# MCU.net
KiCad netlist of a schematic drawn in Altium Designer
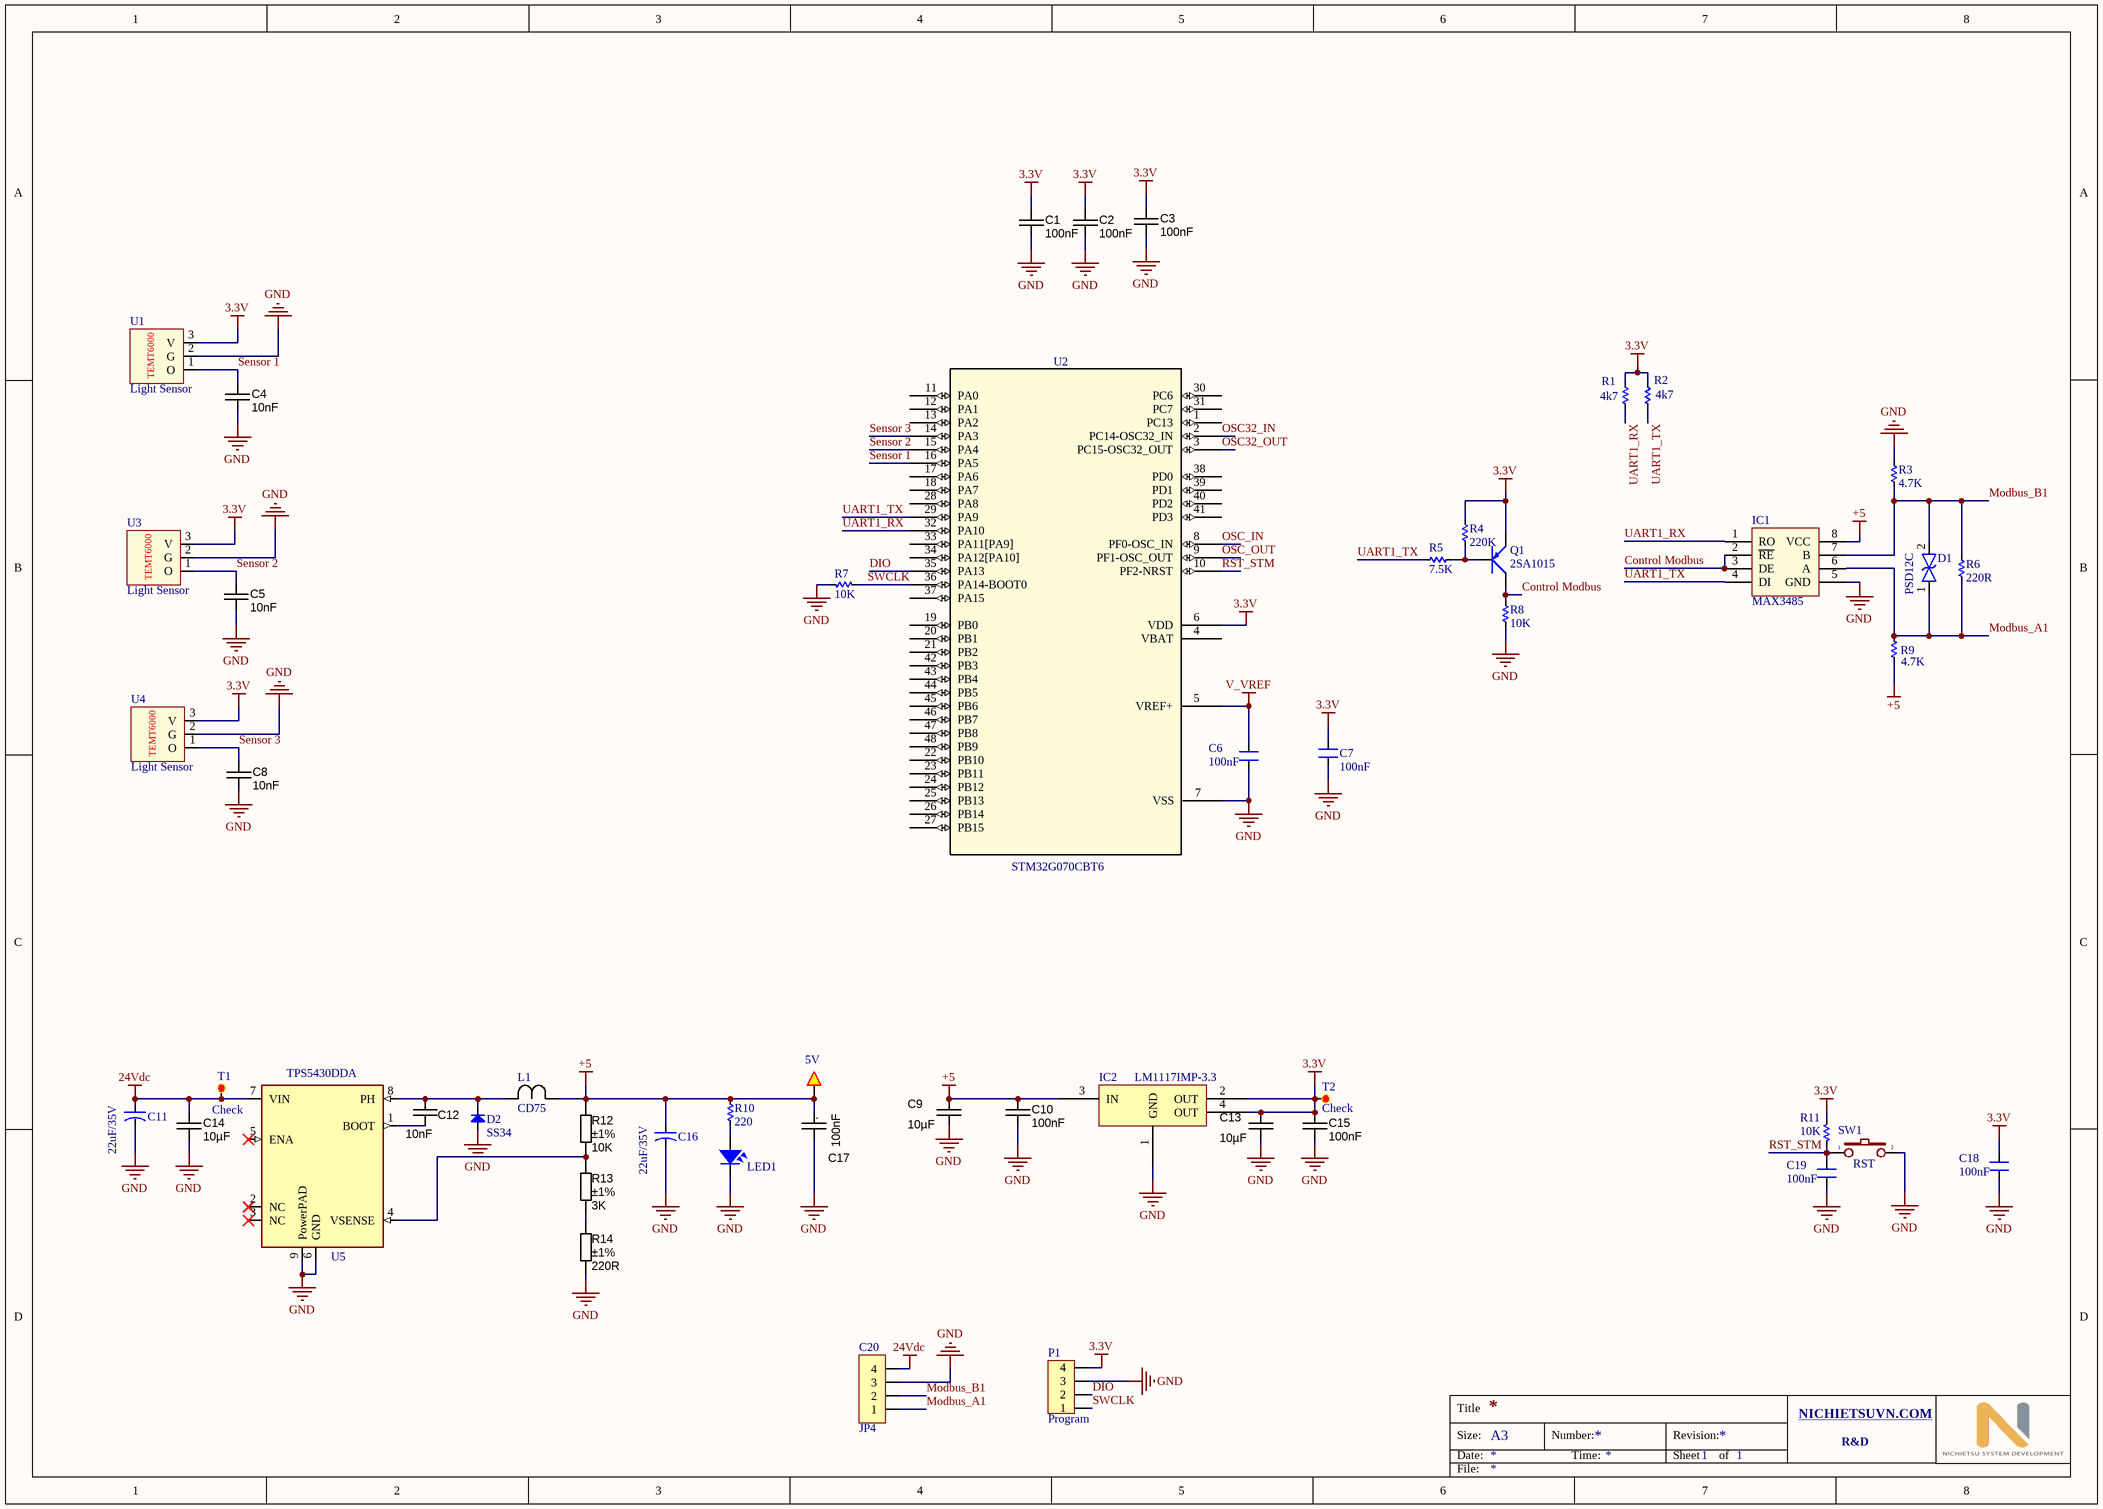
[diagram p0: MCU.SchDoc]

(export (version "E")
  (design (tool "Eeschema 10.0.6"))
  (components
    (comp (ref "C1")
      (value "100nF")
      (footprint "CAPC1608X90N")
      (description "0.1µF ±10% 50V Ceramic Capacitor X7R 0603 (1608 Metric)")
      (fields (field (name "TOLERANCE") "±10%"))
      (libsource (lib "All Library") (part "CAPC_100nF_0603_X7R_50V_10%"))
    )
    (comp (ref "C2")
      (value "100nF")
      (footprint "CAPC1608X90N")
      (description "0.1µF ±10% 50V Ceramic Capacitor X7R 0603 (1608 Metric)")
      (fields (field (name "TOLERANCE") "±10%"))
      (libsource (lib "All Library") (part "CAPC_100nF_0603_X7R_50V_10%"))
    )
    (comp (ref "C3")
      (value "100nF")
      (footprint "CAPC1608X90N")
      (description "0.1µF ±10% 50V Ceramic Capacitor X7R 0603 (1608 Metric)")
      (fields (field (name "TOLERANCE") "±10%"))
      (libsource (lib "All Library") (part "CAPC_100nF_0603_X7R_50V_10%"))
    )
    (comp (ref "C4")
      (value "10nF")
      (footprint "CAPC1608X90N")
      (description "0.1µF ±10% 50V Ceramic Capacitor X7R 0603 (1608 Metric)")
      (fields (field (name "TOLERANCE") "±10%"))
      (libsource (lib "All Library") (part "CAPC_100nF_0603_X7R_50V_10%"))
    )
    (comp (ref "C5")
      (value "10nF")
      (footprint "CAPC1608X90N")
      (description "0.1µF ±10% 50V Ceramic Capacitor X7R 0603 (1608 Metric)")
      (fields (field (name "TOLERANCE") "±10%"))
      (libsource (lib "All Library") (part "CAPC_100nF_0603_X7R_50V_10%"))
    )
    (comp (ref "C6") (value "100nF") (footprint "CN-SMD-0603") (libsource (lib "thu vien 3d") (part "CN")))
    (comp (ref "C7") (value "100nF") (footprint "CN-SMD-0603") (libsource (lib "thu vien 3d") (part "CN")))
    (comp (ref "C8")
      (value "10nF")
      (footprint "CAPC1608X90N")
      (description "0.1µF ±10% 50V Ceramic Capacitor X7R 0603 (1608 Metric)")
      (fields (field (name "TOLERANCE") "±10%"))
      (libsource (lib "All Library") (part "CAPC_100nF_0603_X7R_50V_10%"))
    )
    (comp (ref "C9")
      (value "10µF")
      (footprint "CAPC2012X135N")
      (description "4.7µF ±10% 50V Ceramic Capacitor X7R 0805 (2012 Metric)")
      (fields
        (field (name "TOLERANCE") "±10%")
        (field (name "MANUFACTURER PART NUMBER") "CGA4J1X7R1H475K125AE")
      )
      (libsource (lib "All Library") (part "CAPC_4.7uF_0805_X7R_50V_10%"))
    )
    (comp (ref "C10")
      (value "100nF")
      (footprint "CAPC1608X90N")
      (description "0.1µF ±10% 50V Ceramic Capacitor X7R 0603 (1608 Metric)")
      (fields (field (name "TOLERANCE") "±10%"))
      (libsource (lib "All Library") (part "CAPC_100nF_0603_X7R_50V_10%"))
    )
    (comp (ref "C11")
      (value "22uF/35V")
      (footprint "CA-ALU-2.54")
      (description "Capacitor (Semiconductor SIM Model)")
      (fields (field (name "PUBLISHER") "Altium Limited"))
      (libsource (lib "thu vien 3d") (part "CN-ALU-DIP"))
    )
    (comp (ref "C12")
      (value "10nF")
      (footprint "CAPC1608X90N")
      (description "10000pF ±10% 50V Ceramic Capacitor X7R 0603 (1608 Metric)")
      (fields (field (name "TOLERANCE") "±10%"))
      (libsource (lib "SangMV") (part "CAPC_10000pF_0603_50V_10%"))
    )
    (comp (ref "C13")
      (value "10µF")
      (footprint "CAPC2012X135N")
      (description "4.7µF ±10% 50V Ceramic Capacitor X7R 0805 (2012 Metric)")
      (fields
        (field (name "TOLERANCE") "±10%")
        (field (name "MANUFACTURER PART NUMBER") "CGA4J1X7R1H475K125AE")
      )
      (libsource (lib "All Library") (part "CAPC_4.7uF_0805_X7R_50V_10%"))
    )
    (comp (ref "C14")
      (value "10µF")
      (footprint "CAPC2012X135N")
      (description "10µF ±10% 25V Ceramic Capacitor X7R 1206 (3216 Metric)")
      (fields (field (name "TOLERANCE") "±10%") (field (name "MANUFACTURER PART NUMBER") "TMK316AB7106KLHT"))
      (libsource (lib "All Library") (part "CAPC_10uF_0805_X7R_25V_10%"))
    )
    (comp (ref "C15")
      (value "100nF")
      (footprint "CAPC1608X90N")
      (description "0.1µF ±10% 50V Ceramic Capacitor X7R 0603 (1608 Metric)")
      (fields (field (name "TOLERANCE") "±10%"))
      (libsource (lib "All Library") (part "CAPC_100nF_0603_X7R_50V_10%"))
    )
    (comp (ref "C16")
      (value "22uF/35V")
      (footprint "CA-ALU-2.54")
      (description "Capacitor (Semiconductor SIM Model)")
      (fields (field (name "PUBLISHER") "Altium Limited"))
      (libsource (lib "thu vien 3d") (part "CN-ALU-DIP"))
    )
    (comp (ref "C17")
      (value "100nF")
      (footprint "CAPC2012X135N")
      (description "0.1µF ±10% 50V Ceramic Capacitor X7R 0805 (2012 Metric)")
      (fields (field (name "TOLERANCE") "±10%") (field (name "MANUFACTURER PART NUMBER") "CL21B104KBFXPJE"))
      (libsource (lib "SangMV") (part "CAPC_100nF_0805_X7R_50V_10%"))
    )
    (comp (ref "C18") (value "100nF") (footprint "CN-SMD-0603") (libsource (lib "thu vien 3d") (part "CN")))
    (comp (ref "C19") (value "100nF") (footprint "CN-SMD-0603") (libsource (lib "thu vien 3d") (part "CN")))
    (comp (ref "C20")
      (value "JP4")
      (footprint "JP4-D1C")
      (description "WR-PHD 2.54 mm Angled Socket Header")
      (fields
        (field (name "MANUFACTURER") "Würth Elektronik eiSos GmbH")
        (field (name "PARTNO") "613004143121")
        (field (name "CREATED BY") "Karrer Zheng")
      )
      (libsource (lib "thu vien 3d") (part "JP4"))
    )
    (comp (ref "Check1")
      (value "5V")
      (footprint "SMD-2")
      (description "WR-PHD 2.54 mm Angled Socket Header")
      (fields
        (field (name "MANUFACTURER") "Würth Elektronik eiSos GmbH")
        (field (name "PARTNO") "613002143121")
        (field (name "CREATED BY") "Karrer Zheng")
      )
      (libsource (lib "Nichietsuvn") (part "Test"))
    )
    (comp (ref "D1")
      (value "PSD12C")
      (footprint "PSD12C")
      (description "diode tvs")
      (libsource (lib "Nichietsuvn") (part "PSD12C"))
    )
    (comp (ref "D2")
      (value "SS34")
      (footprint "DIO-SMD-106")
      (description "Default Diode")
      (fields (field (name "PUBLISHER") "Altium Limited"))
      (libsource (lib "thu vien 3d") (part "Diode SMD"))
    )
    (comp (ref "IC1")
      (value "MAX3485")
      (footprint "SO8")
      (description "RS232 - RS485 (Same sn75176)")
      (libsource (lib "thu vien 3d") (part "MAX485"))
    )
    (comp (ref "IC2")
      (value "LM1117IMP-3.3")
      (footprint "SOT223")
      (description "Linear Voltage Regulator IC  1 Output  800mA SOT-223")
      (fields
        (field (name "MANUFACTURER") "Texas Instruments")
        (field (name "MANUFACTURER PART NUMBER") "LM1117IMP-3.3/NOPB")
      )
      (libsource (lib "All Library") (part "IC_LM1117IMP-3.3"))
    )
    (comp (ref "L1") (value "CD75") (footprint "1uH") (libsource (lib "All Library") (part "1uH")))
    (comp (ref "LED1")
      (value "LED")
      (footprint "LED-0805-Blue")
      (libsource (lib "thu vien 3d") (part "LED SMD"))
    )
    (comp (ref "P1")
      (value "Program")
      (footprint "Program_SMD")
      (libsource (lib "All Library") (part "Program"))
    )
    (comp (ref "Q1")
      (value "2SA1015")
      (footprint "SOT23-321")
      (description "PNP 600mW, ECB")
      (libsource (lib "thu vien 3d") (part "2SA1015"))
    )
    (comp (ref "R1")
      (value "4k7")
      (footprint "RES-SMD-0603")
      (description "Resistor")
      (fields
        (field (name "MANUFACTURER") "Generic Components")
        (field (name "PUBLISHER") "Altium Hobart Technology Centre")
      )
      (libsource (lib "thu vien 3d") (part "Res-SMD"))
    )
    (comp (ref "R2")
      (value "4k7")
      (footprint "RES-SMD-0603")
      (description "Resistor")
      (fields
        (field (name "MANUFACTURER") "Generic Components")
        (field (name "PUBLISHER") "Altium Hobart Technology Centre")
      )
      (libsource (lib "thu vien 3d") (part "Res-SMD"))
    )
    (comp (ref "R3")
      (value "4.7K")
      (footprint "RES-SMD-0603")
      (description "Resistor")
      (fields
        (field (name "MANUFACTURER") "Generic Components")
        (field (name "PUBLISHER") "Altium Hobart Technology Centre")
      )
      (libsource (lib "thu vien 3d") (part "Res-SMD"))
    )
    (comp (ref "R4")
      (value "220K")
      (footprint "RES-SMD-0603")
      (description "Resistor")
      (fields
        (field (name "MANUFACTURER") "Generic Components")
        (field (name "PUBLISHER") "Altium Hobart Technology Centre")
      )
      (libsource (lib "thu vien 3d") (part "Res-SMD"))
    )
    (comp (ref "R5")
      (value "7.5K")
      (footprint "RES-SMD-0603")
      (description "Resistor")
      (fields
        (field (name "MANUFACTURER") "Generic Components")
        (field (name "PUBLISHER") "Altium Hobart Technology Centre")
      )
      (libsource (lib "thu vien 3d") (part "Res-SMD"))
    )
    (comp (ref "R6")
      (value "220R")
      (footprint "RES-SMD-0603")
      (description "Resistor")
      (fields
        (field (name "MANUFACTURER") "Generic Components")
        (field (name "PUBLISHER") "Altium Hobart Technology Centre")
      )
      (libsource (lib "thu vien 3d") (part "Res-SMD"))
    )
    (comp (ref "R7")
      (value "10K")
      (footprint "RES-SMD-0603")
      (description "Resistor")
      (fields
        (field (name "MANUFACTURER") "Generic Components")
        (field (name "PUBLISHER") "Altium Hobart Technology Centre")
      )
      (libsource (lib "thu vien 3d") (part "Res-SMD"))
    )
    (comp (ref "R8")
      (value "10K")
      (footprint "RES-SMD-0603")
      (description "Resistor")
      (fields
        (field (name "MANUFACTURER") "Generic Components")
        (field (name "PUBLISHER") "Altium Hobart Technology Centre")
      )
      (libsource (lib "thu vien 3d") (part "Res-SMD"))
    )
    (comp (ref "R9")
      (value "4.7K")
      (footprint "RES-SMD-0603")
      (description "Resistor")
      (fields
        (field (name "MANUFACTURER") "Generic Components")
        (field (name "PUBLISHER") "Altium Hobart Technology Centre")
      )
      (libsource (lib "thu vien 3d") (part "Res-SMD"))
    )
    (comp (ref "R10")
      (value "220")
      (footprint "RES-SMD-0603")
      (description "Resistor")
      (fields
        (field (name "MANUFACTURER") "Generic Components")
        (field (name "PUBLISHER") "Altium Hobart Technology Centre")
      )
      (libsource (lib "thu vien 3d") (part "Res-SMD"))
    )
    (comp (ref "R11")
      (value "10K")
      (footprint "RES-SMD-0603")
      (description "Resistor")
      (fields
        (field (name "MANUFACTURER") "Generic Components")
        (field (name "PUBLISHER") "Altium Hobart Technology Centre")
      )
      (libsource (lib "thu vien 3d") (part "Res-SMD"))
    )
    (comp (ref "R12")
      (value "10K")
      (footprint "RESC1608X55N")
      (fields
        (field (name "MANUFACTURER") "Stackpole Electronics Inc")
        (field (name "MANUFACTURER PART NUMBER") "RMCF0603FT10K0")
        (field (name "TOLERANCE") "±1%")
        (field (name "Comment") "10K_0603_1%")
      )
      (libsource (lib "SangMV") (part "RES_10K_0603_1%"))
    )
    (comp (ref "R13")
      (value "3K")
      (footprint "RESC1608X55N")
      (description "3 kOhms ±1% 0.1W, 1/10W Chip Resistor 0603 (1608 Metric) Automotive AEC-Q200 Thick Film")
      (fields
        (field (name "MANUFACTURER") "Stackpole Electronics Inc")
        (field (name "MANUFACTURER PART NUMBER") "RMCF0603FT3K00")
        (field (name "TOLERANCE") "±1%")
      )
      (libsource (lib "SangMV") (part "RES_3K_0603_1%"))
    )
    (comp (ref "R14")
      (value "220R")
      (footprint "RESC1608X55N")
      (description "220 Ohms ±1% 0.1W, 1/10W Chip Resistor 0603 (1608 Metric) Automotive AEC-Q200 Thick Film")
      (fields
        (field (name "MANUFACTURER") "Stackpole Electronics Inc")
        (field (name "MANUFACTURER PART NUMBER") "RMCF0603FT220R")
        (field (name "TOLERANCE") "±1%")
      )
      (libsource (lib "SangMV") (part "RES_220R_0603_1%"))
    )
    (comp (ref "SW1")
      (value "RST")
      (footprint "SW1-SMD")
      (description "Switch button 2 pin")
      (libsource (lib "thu vien 3d") (part "SW2"))
    )
    (comp (ref "T1")
      (value "Check")
      (footprint "SMD_1.5")
      (description "WR-PHD 2.54 mm Angled Socket Header")
      (fields
        (field (name "MANUFACTURER") "Würth Elektronik eiSos GmbH")
        (field (name "PARTNO") "613002143121")
        (field (name "CREATED BY") "Karrer Zheng")
      )
      (libsource (lib "All Library") (part "Test"))
    )
    (comp (ref "T2")
      (value "Check")
      (footprint "SMD_1.5")
      (description "WR-PHD 2.54 mm Angled Socket Header")
      (fields
        (field (name "MANUFACTURER") "Würth Elektronik eiSos GmbH")
        (field (name "PARTNO") "613002143121")
        (field (name "CREATED BY") "Karrer Zheng")
      )
      (libsource (lib "All Library") (part "Test"))
    )
    (comp (ref "U1")
      (value "Light Sensor")
      (footprint "TEMT6000")
      (description "TEMT6000 Analog Light Sensor")
      (libsource (lib "All Library") (part "TEMT6000"))
    )
    (comp (ref "U2")
      (value "STM32G070CBT6")
      (footprint "STM32G070CBT6")
      (description "No Description Available")
      (fields (field (name "COPYRIGHT") "Copyright (C) 2018 Accelerated Designs. All rights reserved"))
      (libsource (lib "Nichietsuvn") (part "STM32G070CBT6"))
    )
    (comp (ref "U3")
      (value "Light Sensor")
      (footprint "TEMT6000")
      (description "TEMT6000 Analog Light Sensor")
      (libsource (lib "All Library") (part "TEMT6000"))
    )
    (comp (ref "U4")
      (value "Light Sensor")
      (footprint "TEMT6000")
      (description "TEMT6000 Analog Light Sensor")
      (libsource (lib "All Library") (part "TEMT6000"))
    )
    (comp (ref "U5")
      (value "TPS5430DDA")
      (footprint "TPS5430")
      (libsource (lib "Nichietsuvn") (part "TPS5430DDA"))
    )
  )
  (nets
    (net (code "1") (name "+5") (class "Default")
      (node (ref "C10") (pin "1") (pintype "passive"))
      (node (ref "C16") (pin "1") (pinfunction "1_1") (pintype "passive"))
      (node (ref "C17") (pin "1") (pintype "passive"))
      (node (ref "C9") (pin "2") (pintype "passive"))
      (node (ref "Check1") (pin "1") (pinfunction "1_1") (pintype "passive"))
      (node (ref "IC1") (pin "8") (pinfunction "VCC_8") (pintype "passive"))
      (node (ref "IC2") (pin "3") (pinfunction "IN_3") (pintype "passive"))
      (node (ref "L1") (pin "1") (pinfunction "1_1") (pintype "passive"))
      (node (ref "R10") (pin "1") (pinfunction "1_1") (pintype "passive"))
      (node (ref "R12") (pin "2") (pinfunction "2_2") (pintype "passive"))
      (node (ref "R9") (pin "1") (pinfunction "1_1") (pintype "passive"))
    )
    (net (code "2") (name "/Control Modbus") (class "Default")
      (node (ref "IC1") (pin "2") (pinfunction "~{RE}_2") (pintype "passive"))
      (node (ref "IC1") (pin "3") (pinfunction "DE_3") (pintype "passive"))
      (node (ref "Q1") (pin "2") (pinfunction "C_2") (pintype "passive"))
      (node (ref "R8") (pin "2") (pinfunction "2_2") (pintype "passive"))
    )
    (net (code "3") (name "/DIO") (class "Default")
      (node (ref "P1") (pin "2") (pinfunction "2_2") (pintype "passive"))
      (node (ref "U2") (pin "35") (pinfunction "PA13_35") (pintype "bidirectional"))
    )
    (net (code "4") (name "/Modbus_A1") (class "Default")
      (node (ref "C20") (pin "1") (pinfunction "1_1") (pintype "passive"))
      (node (ref "D1") (pin "1") (pinfunction "1_1") (pintype "passive"))
      (node (ref "IC1") (pin "6") (pinfunction "A_6") (pintype "passive"))
      (node (ref "R6") (pin "2") (pinfunction "2_2") (pintype "passive"))
      (node (ref "R9") (pin "2") (pinfunction "2_2") (pintype "passive"))
    )
    (net (code "5") (name "/Modbus_B1") (class "Default")
      (node (ref "C20") (pin "2") (pinfunction "2_2") (pintype "passive"))
      (node (ref "D1") (pin "2") (pinfunction "2_2") (pintype "passive"))
      (node (ref "IC1") (pin "7") (pinfunction "B_7") (pintype "passive"))
      (node (ref "R3") (pin "2") (pinfunction "2_2") (pintype "passive"))
      (node (ref "R6") (pin "1") (pinfunction "1_1") (pintype "passive"))
    )
    (net (code "6") (name "/OSC32_IN") (class "Default")
      (node (ref "U2") (pin "2") (pinfunction "PC14-OSC32_IN_2") (pintype "bidirectional"))
    )
    (net (code "7") (name "/OSC32_OUT") (class "Default")
      (node (ref "U2") (pin "3") (pinfunction "PC15-OSC32_OUT_3") (pintype "bidirectional"))
    )
    (net (code "8") (name "/OSC_IN") (class "Default")
      (node (ref "U2") (pin "8") (pinfunction "PF0-OSC_IN_8") (pintype "bidirectional"))
    )
    (net (code "9") (name "/OSC_OUT") (class "Default")
      (node (ref "U2") (pin "9") (pinfunction "PF1-OSC_OUT_9") (pintype "bidirectional"))
    )
    (net (code "10") (name "/RST_STM") (class "Default")
      (node (ref "C19") (pin "1") (pinfunction "1_1") (pintype "passive"))
      (node (ref "R11") (pin "2") (pinfunction "2_2") (pintype "passive"))
      (node (ref "SW1") (pin "1") (pinfunction "1_1") (pintype "passive"))
      (node (ref "U2") (pin "10") (pinfunction "PF2-NRST_10") (pintype "bidirectional"))
    )
    (net (code "11") (name "/SWCLK") (class "Default")
      (node (ref "P1") (pin "1") (pinfunction "1_1") (pintype "passive"))
      (node (ref "R7") (pin "1") (pinfunction "1_1") (pintype "passive"))
      (node (ref "U2") (pin "36") (pinfunction "PA14-BOOT0_36") (pintype "bidirectional"))
    )
    (net (code "12") (name "/Sensor 1") (class "Default")
      (node (ref "C4") (pin "1") (pintype "passive"))
      (node (ref "U1") (pin "1") (pinfunction "O_1") (pintype "passive"))
      (node (ref "U2") (pin "16") (pinfunction "PA5_16") (pintype "bidirectional"))
    )
    (net (code "13") (name "/Sensor 2") (class "Default")
      (node (ref "C5") (pin "1") (pintype "passive"))
      (node (ref "U2") (pin "15") (pinfunction "PA4_15") (pintype "bidirectional"))
      (node (ref "U3") (pin "1") (pinfunction "O_1") (pintype "passive"))
    )
    (net (code "14") (name "/Sensor 3") (class "Default")
      (node (ref "C8") (pin "1") (pintype "passive"))
      (node (ref "U2") (pin "14") (pinfunction "PA3_14") (pintype "bidirectional"))
      (node (ref "U4") (pin "1") (pinfunction "O_1") (pintype "passive"))
    )
    (net (code "15") (name "/UART1_RX") (class "Default")
      (node (ref "IC1") (pin "1") (pinfunction "RO_1") (pintype "passive"))
      (node (ref "R1") (pin "2") (pinfunction "2_2") (pintype "passive"))
      (node (ref "U2") (pin "32") (pinfunction "PA10_32") (pintype "bidirectional"))
    )
    (net (code "16") (name "/UART1_TX") (class "Default")
      (node (ref "IC1") (pin "4") (pinfunction "DI_4") (pintype "passive"))
      (node (ref "R2") (pin "2") (pinfunction "2_2") (pintype "passive"))
      (node (ref "R5") (pin "1") (pinfunction "1_1") (pintype "passive"))
      (node (ref "U2") (pin "29") (pinfunction "PA9_29") (pintype "bidirectional"))
    )
    (net (code "17") (name "3.3V") (class "Default")
      (node (ref "C1") (pin "1") (pintype "passive"))
      (node (ref "C13") (pin "2") (pintype "passive"))
      (node (ref "C15") (pin "1") (pintype "passive"))
      (node (ref "C18") (pin "1") (pinfunction "1_1") (pintype "passive"))
      (node (ref "C2") (pin "1") (pintype "passive"))
      (node (ref "C3") (pin "1") (pintype "passive"))
      (node (ref "C7") (pin "1") (pinfunction "1_1") (pintype "passive"))
      (node (ref "IC2") (pin "2") (pinfunction "OUT_2") (pintype "passive"))
      (node (ref "IC2") (pin "4") (pinfunction "OUT_4") (pintype "passive"))
      (node (ref "P1") (pin "4") (pinfunction "4_4") (pintype "passive"))
      (node (ref "Q1") (pin "1") (pinfunction "E_1") (pintype "passive"))
      (node (ref "R1") (pin "1") (pinfunction "1_1") (pintype "passive"))
      (node (ref "R11") (pin "1") (pinfunction "1_1") (pintype "passive"))
      (node (ref "R2") (pin "1") (pinfunction "1_1") (pintype "passive"))
      (node (ref "R4") (pin "2") (pinfunction "2_2") (pintype "passive"))
      (node (ref "T2") (pin "1") (pinfunction "1_1") (pintype "passive"))
      (node (ref "U1") (pin "3") (pinfunction "V_3") (pintype "passive"))
      (node (ref "U2") (pin "6") (pinfunction "VDD_6") (pintype "power_in"))
      (node (ref "U3") (pin "3") (pinfunction "V_3") (pintype "passive"))
      (node (ref "U4") (pin "3") (pinfunction "V_3") (pintype "passive"))
    )
    (net (code "18") (name "24Vdc") (class "Default")
      (node (ref "C11") (pin "1") (pinfunction "1_1") (pintype "passive"))
      (node (ref "C14") (pin "2") (pintype "passive"))
      (node (ref "C20") (pin "4") (pinfunction "4_4") (pintype "passive"))
      (node (ref "T1") (pin "1") (pinfunction "1_1") (pintype "passive"))
      (node (ref "U5") (pin "7") (pinfunction "VIN_7") (pintype "power_in"))
    )
    (net (code "19") (name "GND") (class "Default")
      (node (ref "C1") (pin "2") (pintype "passive"))
      (node (ref "C10") (pin "2") (pintype "passive"))
      (node (ref "C11") (pin "2") (pinfunction "2_2") (pintype "passive"))
      (node (ref "C13") (pin "1") (pintype "passive"))
      (node (ref "C14") (pin "1") (pintype "passive"))
      (node (ref "C15") (pin "2") (pintype "passive"))
      (node (ref "C16") (pin "2") (pinfunction "2_2") (pintype "passive"))
      (node (ref "C17") (pin "2") (pintype "passive"))
      (node (ref "C18") (pin "2") (pinfunction "2_2") (pintype "passive"))
      (node (ref "C19") (pin "2") (pinfunction "2_2") (pintype "passive"))
      (node (ref "C2") (pin "2") (pintype "passive"))
      (node (ref "C20") (pin "3") (pinfunction "3_3") (pintype "passive"))
      (node (ref "C3") (pin "2") (pintype "passive"))
      (node (ref "C4") (pin "2") (pintype "passive"))
      (node (ref "C5") (pin "2") (pintype "passive"))
      (node (ref "C6") (pin "2") (pinfunction "2_2") (pintype "passive"))
      (node (ref "C7") (pin "2") (pinfunction "2_2") (pintype "passive"))
      (node (ref "C8") (pin "2") (pintype "passive"))
      (node (ref "C9") (pin "1") (pintype "passive"))
      (node (ref "D2") (pin "1") (pinfunction "A_1") (pintype "passive"))
      (node (ref "IC1") (pin "5") (pinfunction "GND_5") (pintype "passive"))
      (node (ref "IC2") (pin "1") (pinfunction "GND_1") (pintype "passive"))
      (node (ref "LED1") (pin "2") (pinfunction "2_2") (pintype "passive"))
      (node (ref "P1") (pin "3") (pinfunction "3_3") (pintype "passive"))
      (node (ref "R14") (pin "1") (pinfunction "1_1") (pintype "passive"))
      (node (ref "R3") (pin "1") (pinfunction "1_1") (pintype "passive"))
      (node (ref "R7") (pin "2") (pinfunction "2_2") (pintype "passive"))
      (node (ref "R8") (pin "1") (pinfunction "1_1") (pintype "passive"))
      (node (ref "SW1") (pin "2") (pinfunction "2_2") (pintype "passive"))
      (node (ref "U1") (pin "2") (pinfunction "G_2") (pintype "passive"))
      (node (ref "U2") (pin "7") (pinfunction "VSS_7") (pintype "power_in"))
      (node (ref "U3") (pin "2") (pinfunction "G_2") (pintype "passive"))
      (node (ref "U4") (pin "2") (pinfunction "G_2") (pintype "passive"))
      (node (ref "U5") (pin "6") (pinfunction "GND_6") (pintype "power_in"))
      (node (ref "U5") (pin "9") (pinfunction "PowerPAD_9") (pintype "power_in"))
    )
    (net (code "20") (name "Net-(D2-K)") (class "Default")
      (node (ref "C12") (pin "2") (pintype "passive"))
      (node (ref "D2") (pin "2") (pinfunction "K_2") (pintype "passive"))
      (node (ref "L1") (pin "2") (pinfunction "2_2") (pintype "passive"))
      (node (ref "U5") (pin "8") (pinfunction "PH_8") (pintype "input"))
    )
    (net (code "21") (name "Net-(LED1-Pad1)") (class "Default")
      (node (ref "LED1") (pin "1") (pinfunction "1_1") (pintype "passive"))
      (node (ref "R10") (pin "2") (pinfunction "2_2") (pintype "passive"))
    )
    (net (code "22") (name "Net-(Q1-B)") (class "Default")
      (node (ref "Q1") (pin "3") (pinfunction "B_3") (pintype "passive"))
      (node (ref "R4") (pin "1") (pinfunction "1_1") (pintype "passive"))
      (node (ref "R5") (pin "2") (pinfunction "2_2") (pintype "passive"))
    )
    (net (code "23") (name "Net-(R13-Pad1)") (class "Default")
      (node (ref "R13") (pin "1") (pinfunction "1_1") (pintype "passive"))
      (node (ref "R14") (pin "2") (pinfunction "2_2") (pintype "passive"))
    )
    (net (code "24") (name "Net-(U5-BOOT)") (class "Default")
      (node (ref "C12") (pin "1") (pintype "passive"))
      (node (ref "U5") (pin "1") (pinfunction "BOOT_1") (pintype "output"))
    )
    (net (code "25") (name "Net-(U5-VSENSE)") (class "Default")
      (node (ref "R12") (pin "1") (pinfunction "1_1") (pintype "passive"))
      (node (ref "R13") (pin "2") (pinfunction "2_2") (pintype "passive"))
      (node (ref "U5") (pin "4") (pinfunction "VSENSE_4") (pintype "input"))
    )
    (net (code "26") (name "V_VREF") (class "Default")
      (node (ref "C6") (pin "1") (pinfunction "1_1") (pintype "passive"))
      (node (ref "U2") (pin "5") (pinfunction "VREF+_5") (pintype "power_in"))
    )
    (net (code "27") (name "unconnected-(U2-PA0-Pad11)") (class "Default")
      (node (ref "U2") (pin "11") (pinfunction "PA0_11") (pintype "bidirectional"))
    )
    (net (code "28") (name "unconnected-(U2-PA1-Pad12)") (class "Default")
      (node (ref "U2") (pin "12") (pinfunction "PA1_12") (pintype "bidirectional"))
    )
    (net (code "29") (name "unconnected-(U2-PA2-Pad13)") (class "Default")
      (node (ref "U2") (pin "13") (pinfunction "PA2_13") (pintype "bidirectional"))
    )
    (net (code "30") (name "unconnected-(U2-PA6-Pad17)") (class "Default")
      (node (ref "U2") (pin "17") (pinfunction "PA6_17") (pintype "bidirectional"))
    )
    (net (code "31") (name "unconnected-(U2-PA7-Pad18)") (class "Default")
      (node (ref "U2") (pin "18") (pinfunction "PA7_18") (pintype "bidirectional"))
    )
    (net (code "32") (name "unconnected-(U2-PA8-Pad28)") (class "Default")
      (node (ref "U2") (pin "28") (pinfunction "PA8_28") (pintype "bidirectional"))
    )
    (net (code "33") (name "unconnected-(U2-PA11[PA9]-Pad33)") (class "Default")
      (node (ref "U2") (pin "33") (pinfunction "PA11[PA9]_33") (pintype "bidirectional"))
    )
    (net (code "34") (name "unconnected-(U2-PA12[PA10]-Pad34)") (class "Default")
      (node (ref "U2") (pin "34") (pinfunction "PA12[PA10]_34") (pintype "bidirectional"))
    )
    (net (code "35") (name "unconnected-(U2-PA15-Pad37)") (class "Default")
      (node (ref "U2") (pin "37") (pinfunction "PA15_37") (pintype "bidirectional"))
    )
    (net (code "36") (name "unconnected-(U2-PB0-Pad19)") (class "Default")
      (node (ref "U2") (pin "19") (pinfunction "PB0_19") (pintype "bidirectional"))
    )
    (net (code "37") (name "unconnected-(U2-PB1-Pad20)") (class "Default")
      (node (ref "U2") (pin "20") (pinfunction "PB1_20") (pintype "bidirectional"))
    )
    (net (code "38") (name "unconnected-(U2-PB2-Pad21)") (class "Default")
      (node (ref "U2") (pin "21") (pinfunction "PB2_21") (pintype "bidirectional"))
    )
    (net (code "39") (name "unconnected-(U2-PB3-Pad42)") (class "Default")
      (node (ref "U2") (pin "42") (pinfunction "PB3_42") (pintype "bidirectional"))
    )
    (net (code "40") (name "unconnected-(U2-PB4-Pad43)") (class "Default")
      (node (ref "U2") (pin "43") (pinfunction "PB4_43") (pintype "bidirectional"))
    )
    (net (code "41") (name "unconnected-(U2-PB5-Pad44)") (class "Default")
      (node (ref "U2") (pin "44") (pinfunction "PB5_44") (pintype "bidirectional"))
    )
    (net (code "42") (name "unconnected-(U2-PB6-Pad45)") (class "Default")
      (node (ref "U2") (pin "45") (pinfunction "PB6_45") (pintype "bidirectional"))
    )
    (net (code "43") (name "unconnected-(U2-PB7-Pad46)") (class "Default")
      (node (ref "U2") (pin "46") (pinfunction "PB7_46") (pintype "bidirectional"))
    )
    (net (code "44") (name "unconnected-(U2-PB8-Pad47)") (class "Default")
      (node (ref "U2") (pin "47") (pinfunction "PB8_47") (pintype "bidirectional"))
    )
    (net (code "45") (name "unconnected-(U2-PB9-Pad48)") (class "Default")
      (node (ref "U2") (pin "48") (pinfunction "PB9_48") (pintype "bidirectional"))
    )
    (net (code "46") (name "unconnected-(U2-PB10-Pad22)") (class "Default")
      (node (ref "U2") (pin "22") (pinfunction "PB10_22") (pintype "bidirectional"))
    )
    (net (code "47") (name "unconnected-(U2-PB11-Pad23)") (class "Default")
      (node (ref "U2") (pin "23") (pinfunction "PB11_23") (pintype "bidirectional"))
    )
    (net (code "48") (name "unconnected-(U2-PB12-Pad24)") (class "Default")
      (node (ref "U2") (pin "24") (pinfunction "PB12_24") (pintype "bidirectional"))
    )
    (net (code "49") (name "unconnected-(U2-PB13-Pad25)") (class "Default")
      (node (ref "U2") (pin "25") (pinfunction "PB13_25") (pintype "bidirectional"))
    )
    (net (code "50") (name "unconnected-(U2-PB14-Pad26)") (class "Default")
      (node (ref "U2") (pin "26") (pinfunction "PB14_26") (pintype "bidirectional"))
    )
    (net (code "51") (name "unconnected-(U2-PB15-Pad27)") (class "Default")
      (node (ref "U2") (pin "27") (pinfunction "PB15_27") (pintype "bidirectional"))
    )
    (net (code "52") (name "unconnected-(U2-PC6-Pad30)") (class "Default")
      (node (ref "U2") (pin "30") (pinfunction "PC6_30") (pintype "bidirectional"))
    )
    (net (code "53") (name "unconnected-(U2-PC7-Pad31)") (class "Default")
      (node (ref "U2") (pin "31") (pinfunction "PC7_31") (pintype "bidirectional"))
    )
    (net (code "54") (name "unconnected-(U2-PC13-Pad1)") (class "Default")
      (node (ref "U2") (pin "1") (pinfunction "PC13_1") (pintype "bidirectional"))
    )
    (net (code "55") (name "unconnected-(U2-PD0-Pad38)") (class "Default")
      (node (ref "U2") (pin "38") (pinfunction "PD0_38") (pintype "bidirectional"))
    )
    (net (code "56") (name "unconnected-(U2-PD1-Pad39)") (class "Default")
      (node (ref "U2") (pin "39") (pinfunction "PD1_39") (pintype "bidirectional"))
    )
    (net (code "57") (name "unconnected-(U2-PD2-Pad40)") (class "Default")
      (node (ref "U2") (pin "40") (pinfunction "PD2_40") (pintype "bidirectional"))
    )
    (net (code "58") (name "unconnected-(U2-PD3-Pad41)") (class "Default")
      (node (ref "U2") (pin "41") (pinfunction "PD3_41") (pintype "bidirectional"))
    )
    (net (code "59") (name "unconnected-(U2-VBAT-Pad4)") (class "Default")
      (node (ref "U2") (pin "4") (pinfunction "VBAT_4") (pintype "power_in"))
    )
    (net (code "60") (name "unconnected-(U5-ENA-Pad5)") (class "Default")
      (node (ref "U5") (pin "5") (pinfunction "ENA_5") (pintype "input+no_connect"))
    )
    (net (code "61") (name "unconnected-(U5-NC-Pad2)") (class "Default")
      (node (ref "U5") (pin "2") (pinfunction "NC_2") (pintype "passive+no_connect"))
    )
    (net (code "62") (name "unconnected-(U5-NC-Pad3)") (class "Default")
      (node (ref "U5") (pin "3") (pinfunction "NC_3") (pintype "passive+no_connect"))
    )
  )
)
